# MB_sensors.net
KiCad netlist of a schematic drawn in Altium Designer
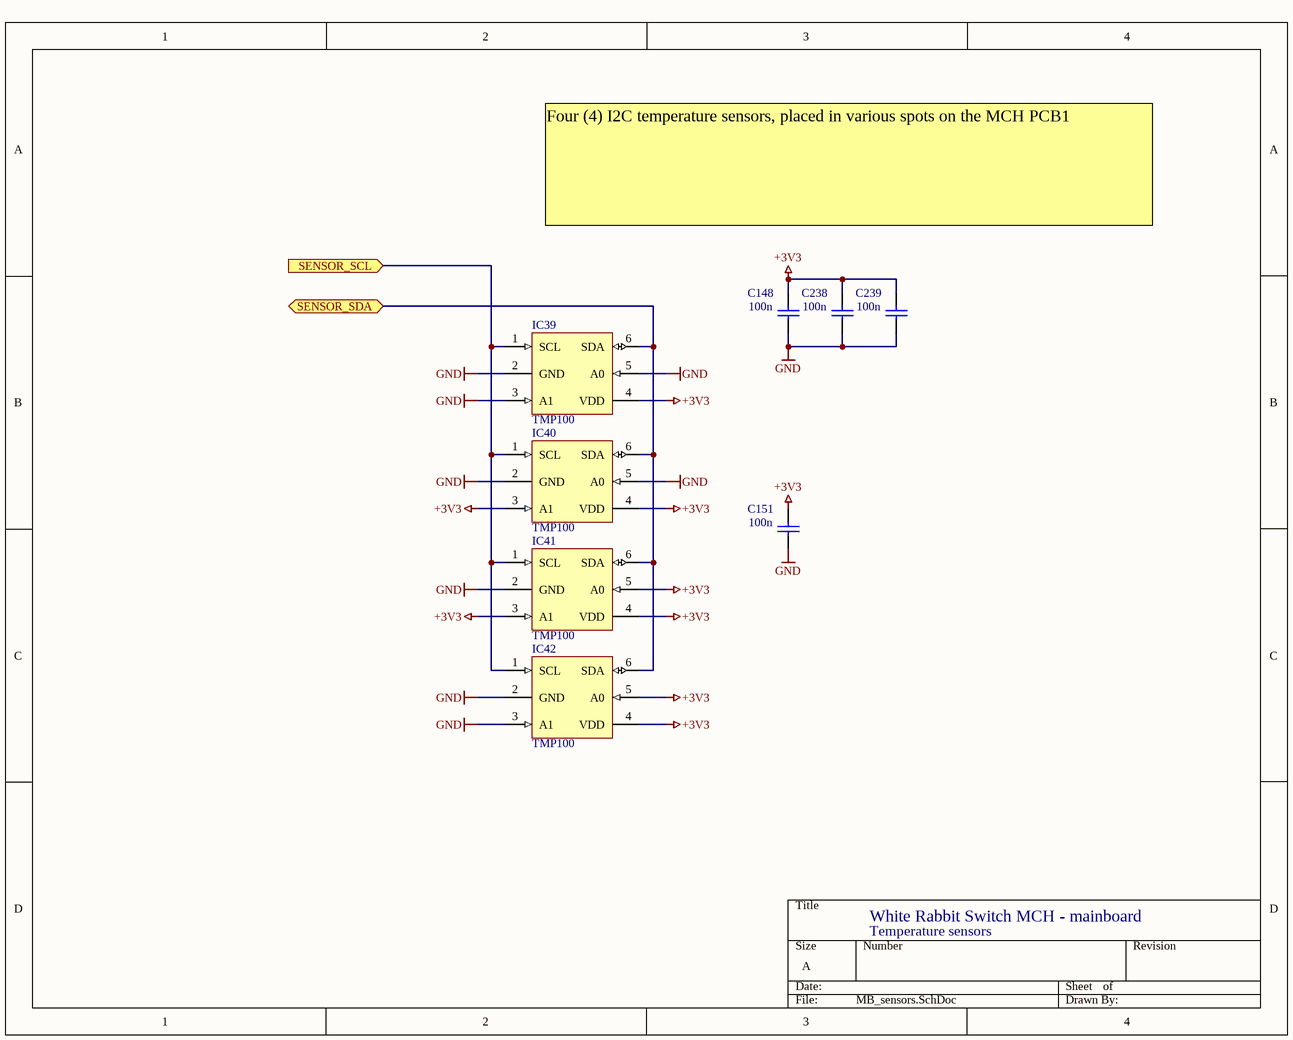
[diagram p0: MB_sensors.SchDoc]

(export (version "E")
  (design (tool "Eeschema 10.0.6"))
  (components
    (comp (ref "C148")
      (value "100n")
      (footprint "CAPC1005X55N")
      (description "Non-polarised capacitor")
      (fields
        (field (name "PART NUMBER") "CC0402_100NF_16V_10%_X7R")
        (field (name "VOLTAGE") "16V")
        (field (name "AUTHOR") "CERN DEM JLC")
      )
      (libsource (lib "Capacitors") (part "Capacitor - non polarized"))
    )
    (comp (ref "C151")
      (value "100n")
      (footprint "CAPC1005X55N")
      (description "Non-polarised capacitor")
      (fields
        (field (name "PART NUMBER") "CC0402_100NF_16V_10%_X7R")
        (field (name "VOLTAGE") "16V")
        (field (name "AUTHOR") "CERN DEM JLC")
      )
      (libsource (lib "Capacitors") (part "Capacitor - non polarized"))
    )
    (comp (ref "C238")
      (value "100n")
      (footprint "CAPC1005X55N")
      (description "Non-polarised capacitor")
      (fields
        (field (name "PART NUMBER") "CC0402_100NF_16V_10%_X7R")
        (field (name "VOLTAGE") "16V")
        (field (name "AUTHOR") "CERN DEM JLC")
      )
      (libsource (lib "Capacitors") (part "Capacitor - non polarized"))
    )
    (comp (ref "C239")
      (value "100n")
      (footprint "CAPC1005X55N")
      (description "Non-polarised capacitor")
      (fields
        (field (name "PART NUMBER") "CC0402_100NF_16V_10%_X7R")
        (field (name "VOLTAGE") "16V")
        (field (name "AUTHOR") "CERN DEM JLC")
      )
      (libsource (lib "Capacitors") (part "Capacitor - non polarized"))
    )
    (comp (ref "IC39")
      (value "TMP100")
      (footprint "SOT23A-6L")
      (description "I2C temp. sensor")
      (libsource (lib "wr_switch") (part "TMP100"))
    )
    (comp (ref "IC40")
      (value "TMP100")
      (footprint "SOT23A-6L")
      (description "I2C temp. sensor")
      (libsource (lib "wr_switch") (part "TMP100"))
    )
    (comp (ref "IC41")
      (value "TMP100")
      (footprint "SOT23A-6L")
      (description "I2C temp. sensor")
      (libsource (lib "wr_switch") (part "TMP100"))
    )
    (comp (ref "IC42")
      (value "TMP100")
      (footprint "SOT23A-6L")
      (description "I2C temp. sensor")
      (libsource (lib "wr_switch") (part "TMP100"))
    )
  )
  (nets
    (net (code "1") (name "+3V3") (class "Default")
      (node (ref "C148") (pin "2") (pinfunction "2_2") (pintype "passive"))
      (node (ref "C151") (pin "2") (pinfunction "2_2") (pintype "passive"))
      (node (ref "C238") (pin "2") (pinfunction "2_2") (pintype "passive"))
      (node (ref "C239") (pin "2") (pinfunction "2_2") (pintype "passive"))
      (node (ref "IC39") (pin "4") (pinfunction "VDD_4") (pintype "power_in"))
      (node (ref "IC40") (pin "3") (pinfunction "A1_3") (pintype "input"))
      (node (ref "IC40") (pin "4") (pinfunction "VDD_4") (pintype "power_in"))
      (node (ref "IC41") (pin "3") (pinfunction "A1_3") (pintype "input"))
      (node (ref "IC41") (pin "4") (pinfunction "VDD_4") (pintype "power_in"))
      (node (ref "IC41") (pin "5") (pinfunction "A0_5") (pintype "input"))
      (node (ref "IC42") (pin "4") (pinfunction "VDD_4") (pintype "power_in"))
      (node (ref "IC42") (pin "5") (pinfunction "A0_5") (pintype "input"))
    )
    (net (code "2") (name "/SENSOR_SCL") (class "Default")
      (node (ref "IC39") (pin "1") (pinfunction "SCL_1") (pintype "input"))
      (node (ref "IC40") (pin "1") (pinfunction "SCL_1") (pintype "input"))
      (node (ref "IC41") (pin "1") (pinfunction "SCL_1") (pintype "input"))
      (node (ref "IC42") (pin "1") (pinfunction "SCL_1") (pintype "input"))
    )
    (net (code "3") (name "/SENSOR_SDA") (class "Default")
      (node (ref "IC39") (pin "6") (pinfunction "SDA_6") (pintype "bidirectional"))
      (node (ref "IC40") (pin "6") (pinfunction "SDA_6") (pintype "bidirectional"))
      (node (ref "IC41") (pin "6") (pinfunction "SDA_6") (pintype "bidirectional"))
      (node (ref "IC42") (pin "6") (pinfunction "SDA_6") (pintype "bidirectional"))
    )
    (net (code "4") (name "GND") (class "Default")
      (node (ref "C148") (pin "1") (pinfunction "1_1") (pintype "passive"))
      (node (ref "C151") (pin "1") (pinfunction "1_1") (pintype "passive"))
      (node (ref "C238") (pin "1") (pinfunction "1_1") (pintype "passive"))
      (node (ref "C239") (pin "1") (pinfunction "1_1") (pintype "passive"))
      (node (ref "IC39") (pin "2") (pinfunction "GND_2") (pintype "power_in"))
      (node (ref "IC39") (pin "3") (pinfunction "A1_3") (pintype "input"))
      (node (ref "IC39") (pin "5") (pinfunction "A0_5") (pintype "input"))
      (node (ref "IC40") (pin "2") (pinfunction "GND_2") (pintype "power_in"))
      (node (ref "IC40") (pin "5") (pinfunction "A0_5") (pintype "input"))
      (node (ref "IC41") (pin "2") (pinfunction "GND_2") (pintype "power_in"))
      (node (ref "IC42") (pin "2") (pinfunction "GND_2") (pintype "power_in"))
      (node (ref "IC42") (pin "3") (pinfunction "A1_3") (pintype "input"))
    )
  )
)
